# Trigger.net
KiCad netlist of a schematic drawn in Altium Designer
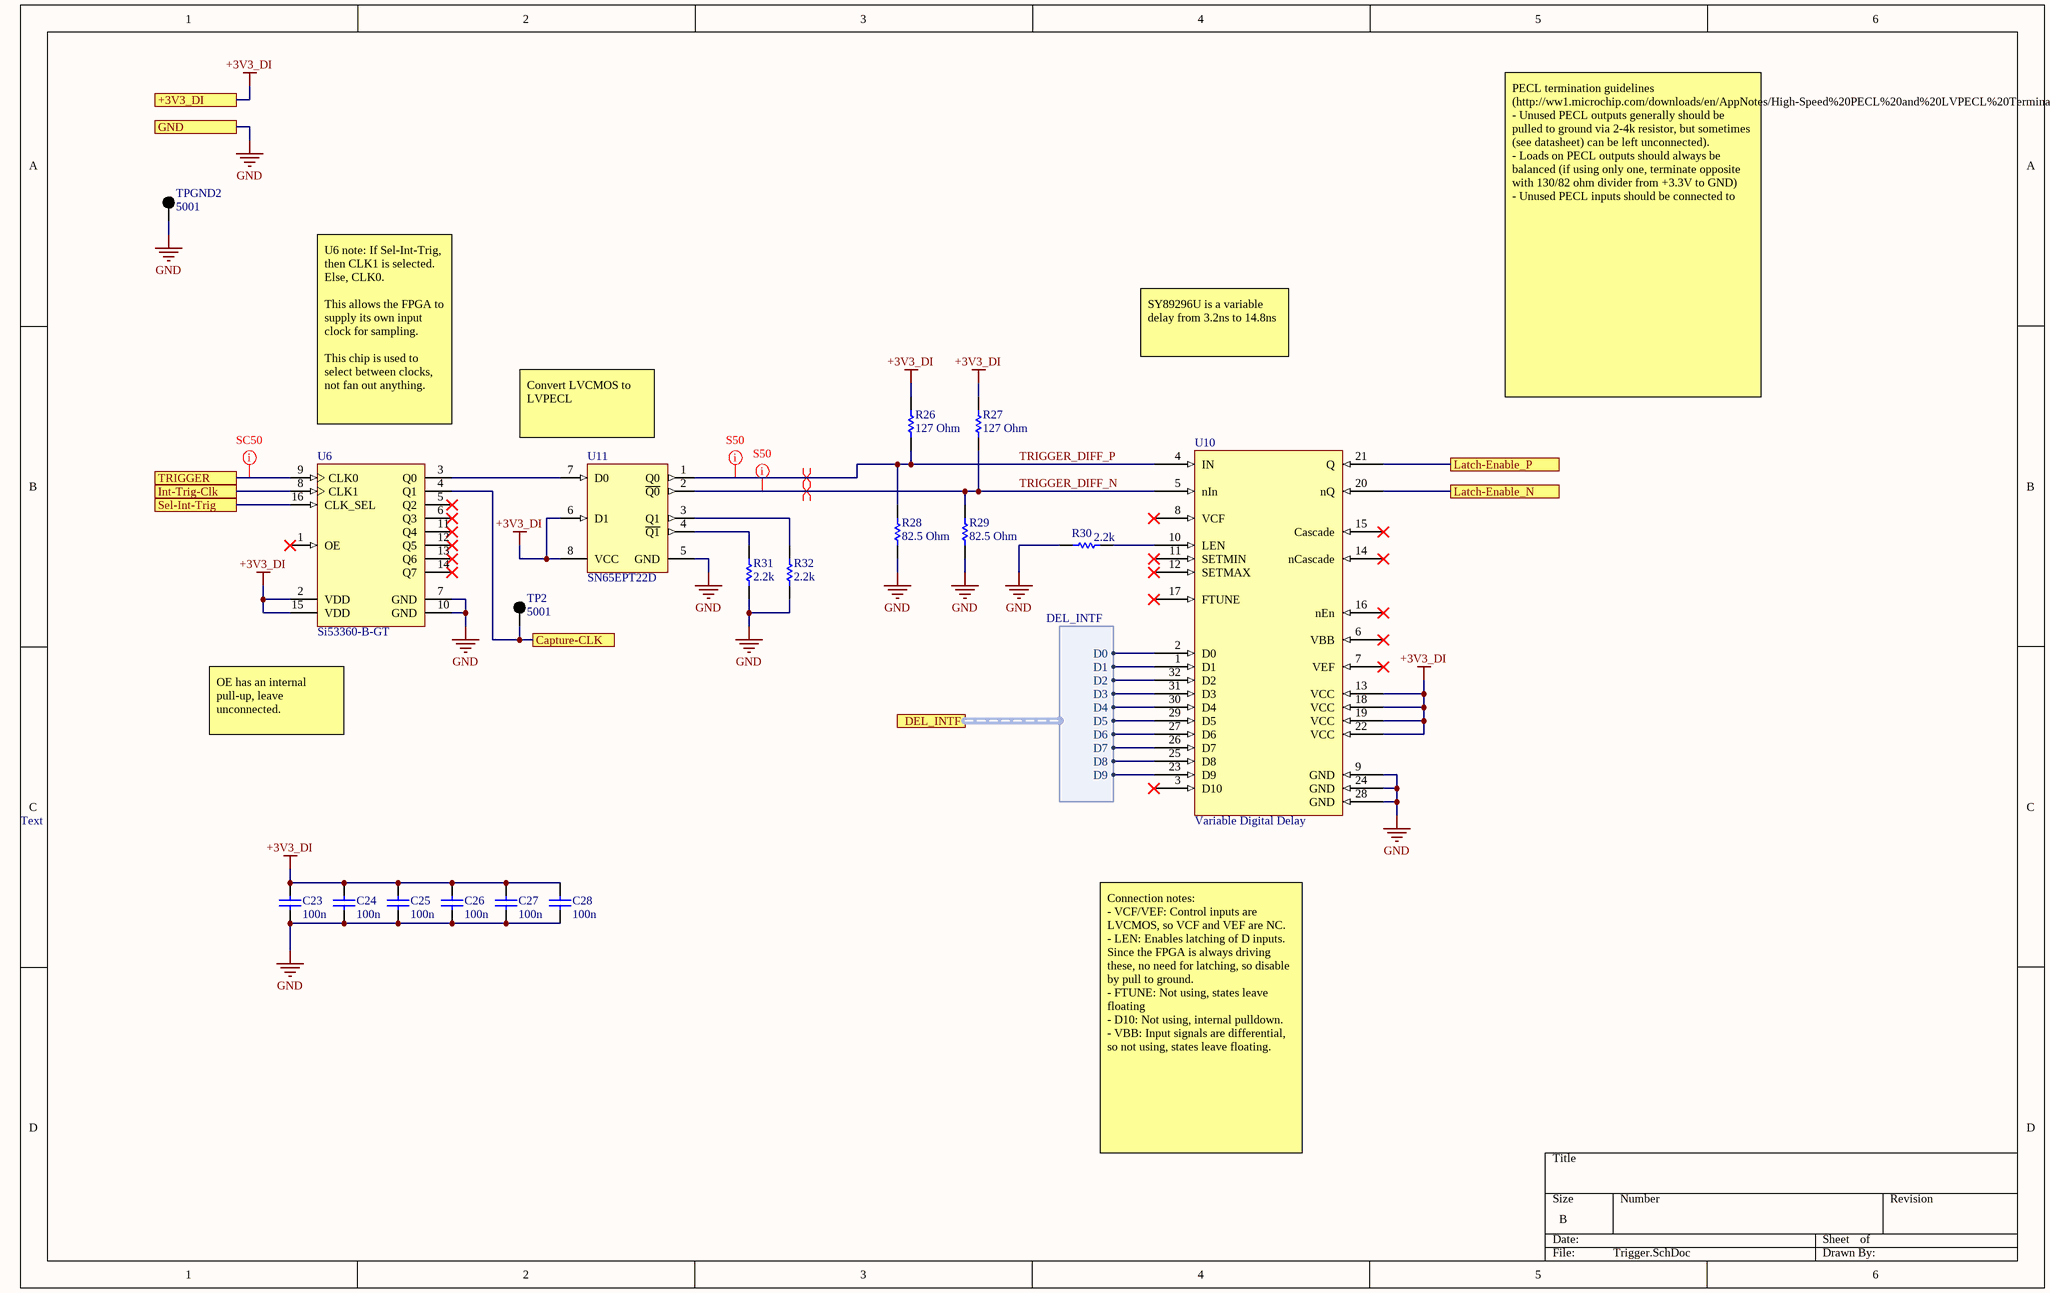
[diagram p0: Trigger.SchDoc]

(export (version "E")
  (design (tool "Eeschema 10.0.6"))
  (components
    (comp (ref "C23")
      (value "100n")
      (footprint "CAPC2013X88X50NL20T25")
      (fields (field (name "PART NUMBER") "C0805C104K5RACTU") (field (name "MANUFACTURER") "Kemet"))
      (libsource (lib "Altium Content Vault") (part "CAP"))
    )
    (comp (ref "C24")
      (value "100n")
      (footprint "CAPC2013X88X50NL20T25")
      (fields (field (name "PART NUMBER") "C0805C104K5RACTU") (field (name "MANUFACTURER") "Kemet"))
      (libsource (lib "Altium Content Vault") (part "CAP"))
    )
    (comp (ref "C25")
      (value "100n")
      (footprint "CAPC2013X88X50NL20T25")
      (fields (field (name "PART NUMBER") "C0805C104K5RACTU") (field (name "MANUFACTURER") "Kemet"))
      (libsource (lib "Altium Content Vault") (part "CAP"))
    )
    (comp (ref "C26")
      (value "100n")
      (footprint "CAPC2013X88X50NL20T25")
      (fields (field (name "PART NUMBER") "C0805C104K5RACTU") (field (name "MANUFACTURER") "Kemet"))
      (libsource (lib "Altium Content Vault") (part "CAP"))
    )
    (comp (ref "C27")
      (value "100n")
      (footprint "CAPC2013X88X50NL20T25")
      (fields (field (name "PART NUMBER") "C0805C104K5RACTU") (field (name "MANUFACTURER") "Kemet"))
      (libsource (lib "Altium Content Vault") (part "CAP"))
    )
    (comp (ref "C28")
      (value "100n")
      (footprint "CAPC2013X88X50NL20T25")
      (fields (field (name "PART NUMBER") "C0805C104K5RACTU") (field (name "MANUFACTURER") "Kemet"))
      (libsource (lib "Altium Content Vault") (part "CAP"))
    )
    (comp (ref "R26")
      (value "127 Ohm")
      (footprint "RESC2013X50X30NL20T20")
      (fields (field (name "MANUFACTURER") "Vishay Dale") (field (name "PART NUMBER") "CRCW0805127RFKEA"))
      (libsource (lib "Altium Content Vault") (part "RES"))
    )
    (comp (ref "R27")
      (value "127 Ohm")
      (footprint "RESC2013X50X30NL20T20")
      (fields (field (name "MANUFACTURER") "Vishay Dale") (field (name "PART NUMBER") "CRCW0805127RFKEA"))
      (libsource (lib "Altium Content Vault") (part "RES"))
    )
    (comp (ref "R28")
      (value "82.5 Ohm")
      (footprint "RESC2013X50X30ML20T20")
      (fields (field (name "PART NUMBER") "CRCW080582R5FKEA") (field (name "MANUFACTURER") "Vishay Dale"))
      (libsource (lib "Altium Content Vault") (part "RES"))
    )
    (comp (ref "R29")
      (value "82.5 Ohm")
      (footprint "RESC2013X50X30ML20T20")
      (fields (field (name "PART NUMBER") "CRCW080582R5FKEA") (field (name "MANUFACTURER") "Vishay Dale"))
      (libsource (lib "Altium Content Vault") (part "RES"))
    )
    (comp (ref "R30")
      (value "2.2k")
      (footprint "RESC2013X50X30NL20T20")
      (fields (field (name "PART NUMBER") "CRCW08052K20FKEA") (field (name "MANUFACTURER") "Vishay Dale"))
      (libsource (lib "Altium Content Vault") (part "RES"))
    )
    (comp (ref "R31")
      (value "2.2k")
      (footprint "RESC2013X50X30NL20T20")
      (fields (field (name "PART NUMBER") "CRCW08052K20FKEA") (field (name "MANUFACTURER") "Vishay Dale"))
      (libsource (lib "Altium Content Vault") (part "RES"))
    )
    (comp (ref "R32")
      (value "2.2k")
      (footprint "RESC2013X50X30NL20T20")
      (fields (field (name "PART NUMBER") "CRCW08052K20FKEA") (field (name "MANUFACTURER") "Vishay Dale"))
      (libsource (lib "Altium Content Vault") (part "RES"))
    )
    (comp (ref "TP2")
      (value "5001")
      (footprint "KSTN-5001")
      (description "Test Point, Black, 1-Pin THD, RoHS, Bulk")
      (fields (field (name "MANUFACTURER") "Keystone"))
      (libsource (lib "Altium Content Vault") (part "KSTN-TP-5001"))
    )
    (comp (ref "TPGND2")
      (value "5001")
      (footprint "KSTN-5001")
      (description "Test Point, Black, 1-Pin THD, RoHS, Bulk")
      (fields (field (name "MANUFACTURER") "Keystone"))
      (libsource (lib "Altium Content Vault") (part "KSTN-TP-5001"))
    )
    (comp (ref "U6")
      (value "Si53360-B-GT")
      (footprint "SLAB-TSSOP-16_M")
      (description "1:8 Low Jitter CMOS Clock Buffer with 2:1 Input Mux, 1 to 200 MHz, -40 to 85 degC, 16-pin SOP")
      (fields (field (name "MANUFACTURER") "Silicon Labs"))
      (libsource (lib "Altium Content Vault") (part "SLAB-Si53360-TSSOP-16-16"))
    )
    (comp (ref "U10")
      (value "Variable Digital Delay")
      (footprint "CQFP80P1115X1115X120-32N")
      (libsource (lib "Local_Parts") (part "SY89296U"))
    )
    (comp (ref "U11")
      (value "SN65EPT22D")
      (footprint "D0008A_M")
      (fields (field (name "MANUFACTURER") "Texas Instruments"))
      (libsource (lib "Altium Content Vault") (part "TI-SN65EPT22-SOIC_D-8"))
    )
  )
  (nets
    (net (code "2") (name "+3V3_DI") (class "Default")
      (node (ref "C23") (pin "2") (pinfunction "2_2") (pintype "passive"))
      (node (ref "C24") (pin "2") (pinfunction "2_2") (pintype "passive"))
      (node (ref "C25") (pin "2") (pinfunction "2_2") (pintype "passive"))
      (node (ref "C26") (pin "2") (pinfunction "2_2") (pintype "passive"))
      (node (ref "C27") (pin "2") (pinfunction "2_2") (pintype "passive"))
      (node (ref "C28") (pin "2") (pinfunction "2_2") (pintype "passive"))
      (node (ref "R26") (pin "2") (pinfunction "2_2") (pintype "passive"))
      (node (ref "R27") (pin "2") (pinfunction "2_2") (pintype "passive"))
      (node (ref "U10") (pin "13") (pinfunction "VCC_13") (pintype "input"))
      (node (ref "U10") (pin "18") (pinfunction "VCC_18") (pintype "input"))
      (node (ref "U10") (pin "19") (pinfunction "VCC_19") (pintype "input"))
      (node (ref "U10") (pin "22") (pinfunction "VCC_22") (pintype "input"))
      (node (ref "U11") (pin "6") (pinfunction "D1_6") (pintype "input"))
      (node (ref "U11") (pin "8") (pinfunction "VCC_8") (pintype "power_in"))
      (node (ref "U6") (pin "15") (pinfunction "VDD_15") (pintype "power_in"))
      (node (ref "U6") (pin "2") (pinfunction "VDD_2") (pintype "power_in"))
    )
    (net (code "3") (name "/Capture-CLK") (class "Default")
      (node (ref "TP2") (pin "1") (pintype "passive"))
      (node (ref "U6") (pin "4") (pinfunction "Q1_4") (pintype "tri_state"))
    )
    (net (code "4") (name "/D0") (class "Default")
      (node (ref "U10") (pin "2") (pinfunction "D0_2") (pintype "input"))
    )
    (net (code "5") (name "/D1") (class "Default")
      (node (ref "U10") (pin "1") (pinfunction "D1_1") (pintype "input"))
    )
    (net (code "6") (name "/D2") (class "Default")
      (node (ref "U10") (pin "32") (pinfunction "D2_32") (pintype "input"))
    )
    (net (code "7") (name "/D3") (class "Default")
      (node (ref "U10") (pin "31") (pinfunction "D3_31") (pintype "input"))
    )
    (net (code "8") (name "/D4") (class "Default")
      (node (ref "U10") (pin "30") (pinfunction "D4_30") (pintype "input"))
    )
    (net (code "9") (name "/D5") (class "Default")
      (node (ref "U10") (pin "29") (pinfunction "D5_29") (pintype "input"))
    )
    (net (code "10") (name "/D6") (class "Default")
      (node (ref "U10") (pin "27") (pinfunction "D6_27") (pintype "input"))
    )
    (net (code "11") (name "/D7") (class "Default")
      (node (ref "U10") (pin "26") (pinfunction "D7_26") (pintype "input"))
    )
    (net (code "12") (name "/D8") (class "Default")
      (node (ref "U10") (pin "25") (pinfunction "D8_25") (pintype "input"))
    )
    (net (code "13") (name "/D9") (class "Default")
      (node (ref "U10") (pin "23") (pinfunction "D9_23") (pintype "input"))
    )
    (net (code "14") (name "/Int-Trig-Clk") (class "Default")
      (node (ref "U6") (pin "8") (pinfunction "CLK1_8") (pintype "input"))
    )
    (net (code "15") (name "/Latch-Enable_N") (class "Default")
      (node (ref "U10") (pin "20") (pinfunction "nQ_20") (pintype "input"))
    )
    (net (code "16") (name "/Latch-Enable_P") (class "Default")
      (node (ref "U10") (pin "21") (pinfunction "Q_21") (pintype "input"))
    )
    (net (code "17") (name "/Sel-Int-Trig") (class "Default")
      (node (ref "U6") (pin "16") (pinfunction "CLK_SEL_16") (pintype "input"))
    )
    (net (code "18") (name "/TRIGGER") (class "Default")
      (node (ref "U6") (pin "9") (pinfunction "CLK0_9") (pintype "input"))
    )
    (net (code "19") (name "/TRIGGER_DIFF_N") (class "Default")
      (node (ref "R27") (pin "1") (pinfunction "1_1") (pintype "passive"))
      (node (ref "R29") (pin "2") (pinfunction "2_2") (pintype "passive"))
      (node (ref "U10") (pin "5") (pinfunction "nIn_5") (pintype "input"))
      (node (ref "U11") (pin "2") (pinfunction "~{Q0}_2") (pintype "output"))
    )
    (net (code "20") (name "/TRIGGER_DIFF_P") (class "Default")
      (node (ref "R26") (pin "1") (pinfunction "1_1") (pintype "passive"))
      (node (ref "R28") (pin "2") (pinfunction "2_2") (pintype "passive"))
      (node (ref "U10") (pin "4") (pinfunction "IN_4") (pintype "input"))
      (node (ref "U11") (pin "1") (pinfunction "Q0_1") (pintype "output"))
    )
    (net (code "22") (name "GND") (class "Default")
      (node (ref "C23") (pin "1") (pinfunction "1_1") (pintype "passive"))
      (node (ref "C24") (pin "1") (pinfunction "1_1") (pintype "passive"))
      (node (ref "C25") (pin "1") (pinfunction "1_1") (pintype "passive"))
      (node (ref "C26") (pin "1") (pinfunction "1_1") (pintype "passive"))
      (node (ref "C27") (pin "1") (pinfunction "1_1") (pintype "passive"))
      (node (ref "C28") (pin "1") (pinfunction "1_1") (pintype "passive"))
      (node (ref "R28") (pin "1") (pinfunction "1_1") (pintype "passive"))
      (node (ref "R29") (pin "1") (pinfunction "1_1") (pintype "passive"))
      (node (ref "R30") (pin "1") (pinfunction "1_1") (pintype "passive"))
      (node (ref "R31") (pin "2") (pinfunction "2_2") (pintype "passive"))
      (node (ref "R32") (pin "2") (pinfunction "2_2") (pintype "passive"))
      (node (ref "TPGND2") (pin "1") (pintype "passive"))
      (node (ref "U10") (pin "24") (pinfunction "GND_24") (pintype "input"))
      (node (ref "U10") (pin "28") (pinfunction "GND_28") (pintype "input"))
      (node (ref "U10") (pin "9") (pinfunction "GND_9") (pintype "input"))
      (node (ref "U11") (pin "5") (pinfunction "GND_5") (pintype "power_in"))
      (node (ref "U6") (pin "10") (pinfunction "GND_10") (pintype "power_in"))
      (node (ref "U6") (pin "7") (pinfunction "GND_7") (pintype "power_in"))
    )
    (net (code "23") (name "Net-(U10-LEN)") (class "Default")
      (node (ref "R30") (pin "2") (pinfunction "2_2") (pintype "passive"))
      (node (ref "U10") (pin "10") (pinfunction "LEN_10") (pintype "input"))
    )
    (net (code "24") (name "Net-(U11-D0)") (class "Default")
      (node (ref "U11") (pin "7") (pinfunction "D0_7") (pintype "input"))
      (node (ref "U6") (pin "3") (pinfunction "Q0_3") (pintype "tri_state"))
    )
    (net (code "25") (name "Net-(U11-Q1)") (class "Default")
      (node (ref "R32") (pin "1") (pinfunction "1_1") (pintype "passive"))
      (node (ref "U11") (pin "3") (pinfunction "Q1_3") (pintype "output"))
    )
    (net (code "26") (name "Net-(U11-~{Q1})") (class "Default")
      (node (ref "R31") (pin "1") (pinfunction "1_1") (pintype "passive"))
      (node (ref "U11") (pin "4") (pinfunction "~{Q1}_4") (pintype "output"))
    )
    (net (code "27") (name "unconnected-(U6-OE-Pad1)") (class "Default")
      (node (ref "U6") (pin "1") (pinfunction "OE_1") (pintype "input+no_connect"))
    )
    (net (code "28") (name "unconnected-(U6-Q2-Pad5)") (class "Default")
      (node (ref "U6") (pin "5") (pinfunction "Q2_5") (pintype "tri_state+no_connect"))
    )
    (net (code "29") (name "unconnected-(U6-Q3-Pad6)") (class "Default")
      (node (ref "U6") (pin "6") (pinfunction "Q3_6") (pintype "tri_state+no_connect"))
    )
    (net (code "30") (name "unconnected-(U6-Q4-Pad11)") (class "Default")
      (node (ref "U6") (pin "11") (pinfunction "Q4_11") (pintype "tri_state+no_connect"))
    )
    (net (code "31") (name "unconnected-(U6-Q5-Pad12)") (class "Default")
      (node (ref "U6") (pin "12") (pinfunction "Q5_12") (pintype "tri_state+no_connect"))
    )
    (net (code "32") (name "unconnected-(U6-Q6-Pad13)") (class "Default")
      (node (ref "U6") (pin "13") (pinfunction "Q6_13") (pintype "tri_state+no_connect"))
    )
    (net (code "33") (name "unconnected-(U6-Q7-Pad14)") (class "Default")
      (node (ref "U6") (pin "14") (pinfunction "Q7_14") (pintype "tri_state+no_connect"))
    )
    (net (code "34") (name "unconnected-(U10-Cascade-Pad15)") (class "Default")
      (node (ref "U10") (pin "15") (pinfunction "Cascade_15") (pintype "input+no_connect"))
    )
    (net (code "35") (name "unconnected-(U10-D10-Pad3)") (class "Default")
      (node (ref "U10") (pin "3") (pinfunction "D10_3") (pintype "input+no_connect"))
    )
    (net (code "36") (name "unconnected-(U10-FTUNE-Pad17)") (class "Default")
      (node (ref "U10") (pin "17") (pinfunction "FTUNE_17") (pintype "input+no_connect"))
    )
    (net (code "37") (name "unconnected-(U10-SETMAX-Pad12)") (class "Default")
      (node (ref "U10") (pin "12") (pinfunction "SETMAX_12") (pintype "input+no_connect"))
    )
    (net (code "38") (name "unconnected-(U10-SETMIN-Pad11)") (class "Default")
      (node (ref "U10") (pin "11") (pinfunction "SETMIN_11") (pintype "input+no_connect"))
    )
    (net (code "39") (name "unconnected-(U10-VBB-Pad6)") (class "Default")
      (node (ref "U10") (pin "6") (pinfunction "VBB_6") (pintype "input+no_connect"))
    )
    (net (code "40") (name "unconnected-(U10-VCF-Pad8)") (class "Default")
      (node (ref "U10") (pin "8") (pinfunction "VCF_8") (pintype "input+no_connect"))
    )
    (net (code "41") (name "unconnected-(U10-VEF-Pad7)") (class "Default")
      (node (ref "U10") (pin "7") (pinfunction "VEF_7") (pintype "input+no_connect"))
    )
    (net (code "42") (name "unconnected-(U10-nCascade-Pad14)") (class "Default")
      (node (ref "U10") (pin "14") (pinfunction "nCascade_14") (pintype "input+no_connect"))
    )
    (net (code "43") (name "unconnected-(U10-nEn-Pad16)") (class "Default")
      (node (ref "U10") (pin "16") (pinfunction "nEn_16") (pintype "input+no_connect"))
    )
  )
)
